# adafruit_flora_mainboard_2.net
KiCad netlist of a schematic drawn in Altium Designer
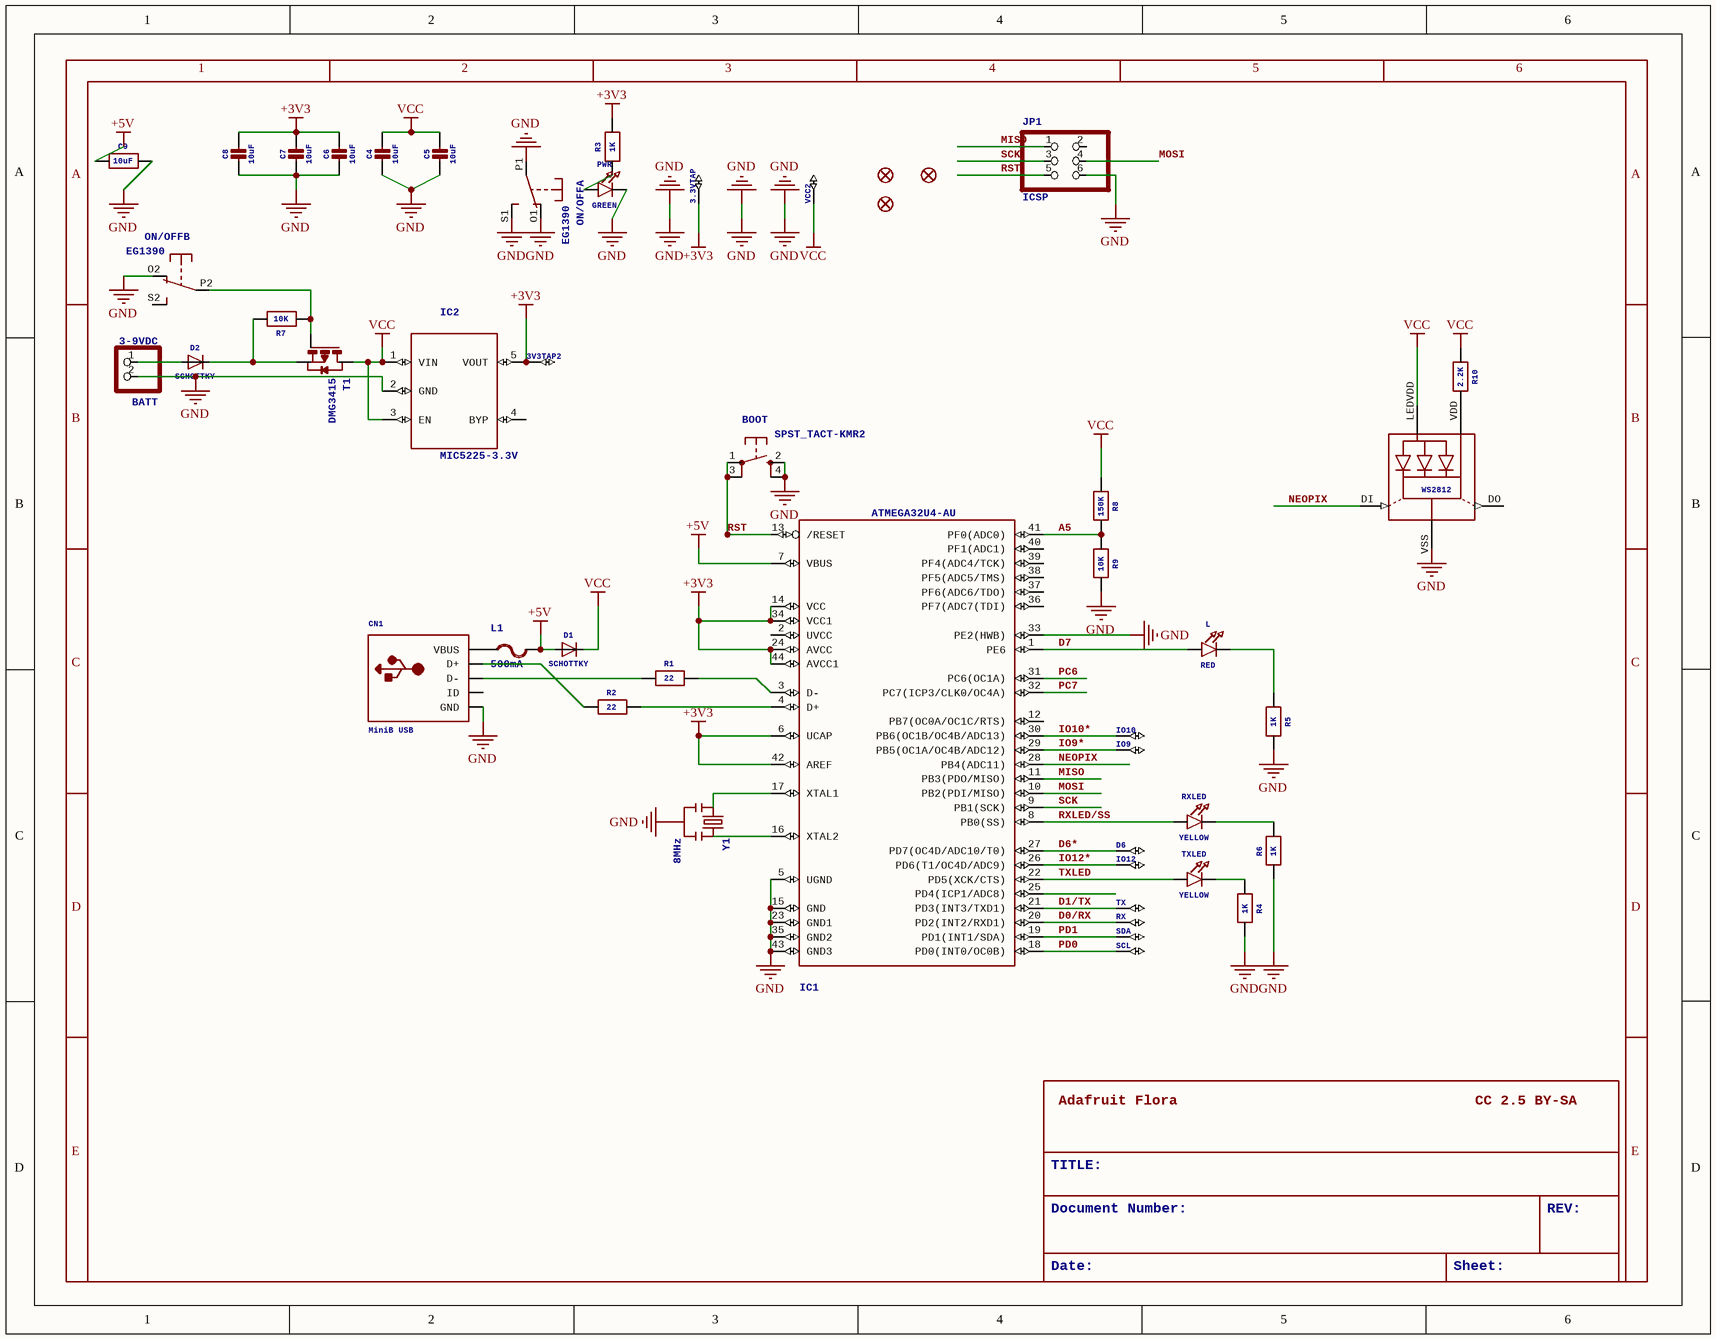
[diagram p0: adafruit flora mainboard 2.SchDoc]

(export (version "E")
  (design (tool "Eeschema 10.0.6"))
  (components
    (comp (ref "3.3VTAP")
      (value "SEWTAP-2.0IN")
      (footprint "SEWINGTAP_2.0")
      (libsource (lib "adafruit") (part "SEWTAP-2.0IN"))
    )
    (comp (ref "3V3TAP2")
      (value "SEWTAP-2.0IN")
      (footprint "SEWINGTAP_2.0")
      (libsource (lib "adafruit") (part "SEWTAP-2.0IN"))
    )
    (comp (ref "BATT")
      (value "3-9VDC")
      (footprint "JST-PH-2-SMT-RA")
      (libsource (lib "adafruit") (part "JST_2PIN-SMT-RA"))
    )
    (comp (ref "BOOT")
      (value "SPST_TACT-KMR2")
      (footprint "KMR2")
      (description "SMT 6mm switch, EVQQ2 series    http://www.ladyada.net/library/eagle")
      (libsource (lib "adafruit") (part "SPST_TACT-KMR2"))
    )
    (comp (ref "C4")
      (value "10uF")
      (footprint "0805-NO")
      (libsource (lib "microbuilder") (part "CAP_CERAMIC0805-NOOUTLINE"))
    )
    (comp (ref "C5")
      (value "10uF")
      (footprint "0805-NO")
      (libsource (lib "microbuilder") (part "CAP_CERAMIC0805-NOOUTLINE"))
    )
    (comp (ref "C6")
      (value "10uF")
      (footprint "0805-NO")
      (libsource (lib "microbuilder") (part "CAP_CERAMIC0805-NOOUTLINE"))
    )
    (comp (ref "C7")
      (value "10uF")
      (footprint "0805-NO")
      (libsource (lib "microbuilder") (part "CAP_CERAMIC0805-NOOUTLINE"))
    )
    (comp (ref "C8")
      (value "10uF")
      (footprint "0805-NO")
      (libsource (lib "microbuilder") (part "CAP_CERAMIC0805-NOOUTLINE"))
    )
    (comp (ref "C9")
      (value "10uF")
      (footprint "_0805MP")
      (libsource (lib "microbuilder") (part "RESISTOR_0805MP"))
    )
    (comp (ref "CN1")
      (value "MiniB USB")
      (footprint "4UCONN_20329")
      (description "USB ConnectorsUSBMINIB - Surface Mount Female Mini-B USB Connector    4UConnector: 06564")
      (libsource (lib "microbuilder") (part "USBMICRO_20329"))
    )
    (comp (ref "D1")
      (value "SCHOTTKY")
      (footprint "SOD-123")
      (libsource (lib "microbuilder") (part "DIODESOD-123"))
    )
    (comp (ref "D2")
      (value "SCHOTTKY")
      (footprint "SOD-123")
      (libsource (lib "microbuilder") (part "DIODESOD-123"))
    )
    (comp (ref "D6")
      (value "SEWTAP-2.0IN")
      (footprint "SEWINGTAP_2.0")
      (libsource (lib "adafruit") (part "SEWTAP-2.0IN"))
    )
    (comp (ref "IC1")
      (value "ATMEGA32U4-AU")
      (footprint "TQFP44")
      (fields (field (name "LIBRARYNAME") "adaprog"))
      (libsource (lib "adaprog") (part "ATMEGA32U4-AU"))
    )
    (comp (ref "IC2")
      (value "MIC5225-3.3V")
      (footprint "SOT23-5L")
      (libsource (lib "adafruit") (part "LP298XS"))
    )
    (comp (ref "IO9")
      (value "SEWTAP-2.0IN")
      (footprint "SEWINGTAP_2.0")
      (libsource (lib "adafruit") (part "SEWTAP-2.0IN"))
    )
    (comp (ref "IO10")
      (value "SEWTAP-2.0IN")
      (footprint "SEWINGTAP_2.0")
      (libsource (lib "adafruit") (part "SEWTAP-2.0IN"))
    )
    (comp (ref "IO12")
      (value "SEWTAP-2.0IN")
      (footprint "SEWINGTAP_2.0")
      (libsource (lib "adafruit") (part "SEWTAP-2.0IN"))
    )
    (comp (ref "JP1")
      (value "ICSP")
      (footprint "2X03")
      (description "PIN HEADER")
      (fields (field (name "LIBRARYNAME") "pinhead"))
      (libsource (lib "pinhead") (part "PINHD-2X3"))
    )
    (comp (ref "L")
      (value "RED")
      (footprint "CHIPLED_0805_NOOUTLINE")
      (libsource (lib "microbuilder") (part "LED0805_NOOUTLINE"))
    )
    (comp (ref "L1")
      (value "500mA")
      (footprint "R1206")
      (description "PTC fuses, resettable thermistors")
      (libsource (lib "adafruit") (part "PTCFUSE-1206"))
    )
    (comp (ref "LED1")
      (value "WS2812")
      (footprint "WS2812")
      (fields (field (name "WS2812") "WS2812"))
      (libsource (lib "adafruit") (part "WS2812"))
    )
    (comp (ref "ON/OFF")
      (value "EG1390")
      (footprint "EG1390")
      (libsource (lib "adafruit") (part "DPDT-EG1390"))
    )
    (comp (ref "PWR")
      (value "GREEN")
      (footprint "CHIPLED_0805_NOOUTLINE")
      (libsource (lib "microbuilder") (part "LED0805_NOOUTLINE"))
    )
    (comp (ref "R1")
      (value "22")
      (footprint "0805-NO")
      (libsource (lib "microbuilder") (part "RESISTOR0805_NOOUTLINE"))
    )
    (comp (ref "R2")
      (value "22")
      (footprint "0805-NO")
      (libsource (lib "microbuilder") (part "RESISTOR0805_NOOUTLINE"))
    )
    (comp (ref "R3")
      (value "1K")
      (footprint "_0805MP")
      (libsource (lib "microbuilder") (part "RESISTOR_0805MP"))
    )
    (comp (ref "R4")
      (value "1K")
      (footprint "_0805MP")
      (libsource (lib "microbuilder") (part "RESISTOR_0805MP"))
    )
    (comp (ref "R5")
      (value "1K")
      (footprint "0805-NO")
      (libsource (lib "microbuilder") (part "RESISTOR0805_NOOUTLINE"))
    )
    (comp (ref "R6")
      (value "1K")
      (footprint "0805-NO")
      (libsource (lib "microbuilder") (part "RESISTOR0805_NOOUTLINE"))
    )
    (comp (ref "R7")
      (value "10K")
      (footprint "_0805MP")
      (libsource (lib "microbuilder") (part "RESISTOR_0805MP"))
    )
    (comp (ref "R8")
      (value "150K")
      (footprint "0805-NO")
      (libsource (lib "microbuilder") (part "RESISTOR0805_NOOUTLINE"))
    )
    (comp (ref "R9")
      (value "10K")
      (footprint "0805-NO")
      (libsource (lib "microbuilder") (part "RESISTOR0805_NOOUTLINE"))
    )
    (comp (ref "R10")
      (value "2.2K")
      (footprint "0805-NO")
      (libsource (lib "microbuilder") (part "RESISTOR0805_NOOUTLINE"))
    )
    (comp (ref "RX")
      (value "SEWTAP-2.0IN")
      (footprint "SEWINGTAP_2.0")
      (libsource (lib "adafruit") (part "SEWTAP-2.0IN"))
    )
    (comp (ref "RXLED")
      (value "YELLOW")
      (footprint "CHIPLED_0805_NOOUTLINE")
      (libsource (lib "microbuilder") (part "LED0805_NOOUTLINE"))
    )
    (comp (ref "SCL")
      (value "SEWTAP-2.0IN")
      (footprint "SEWINGTAP_2.0")
      (libsource (lib "adafruit") (part "SEWTAP-2.0IN"))
    )
    (comp (ref "SDA")
      (value "SEWTAP-2.0IN")
      (footprint "SEWINGTAP_2.0")
      (libsource (lib "adafruit") (part "SEWTAP-2.0IN"))
    )
    (comp (ref "T1")
      (value "DMG3415")
      (footprint "SOT-23")
      (description "MOS FET")
      (libsource (lib "zetex") (part "PMOSSOT23"))
    )
    (comp (ref "TX")
      (value "SEWTAP-2.0IN")
      (footprint "SEWINGTAP_2.0")
      (libsource (lib "adafruit") (part "SEWTAP-2.0IN"))
    )
    (comp (ref "TXLED")
      (value "YELLOW")
      (footprint "CHIPLED_0805_NOOUTLINE")
      (libsource (lib "microbuilder") (part "LED0805_NOOUTLINE"))
    )
    (comp (ref "U$2")
      (value "FIDUCIAL\"\"")
      (footprint "FIDUCIAL_1MM")
      (description "Fiducial Alignment Points   Various fiducial points for machine vision alignment.")
      (libsource (lib "microbuilder") (part "FIDUCIAL{dblquote}{dblquote}"))
    )
    (comp (ref "U$3")
      (value "FIDUCIAL\"\"")
      (footprint "FIDUCIAL_1MM")
      (description "Fiducial Alignment Points   Various fiducial points for machine vision alignment.")
      (libsource (lib "microbuilder") (part "FIDUCIAL{dblquote}{dblquote}"))
    )
    (comp (ref "U$6")
      (value "FIDUCIAL\"\"")
      (footprint "FIDUCIAL_1MM")
      (description "Fiducial Alignment Points   Various fiducial points for machine vision alignment.")
      (libsource (lib "microbuilder") (part "FIDUCIAL{dblquote}{dblquote}"))
    )
    (comp (ref "VCC2")
      (value "SEWTAP-2.0IN")
      (footprint "SEWINGTAP_2.0")
      (libsource (lib "adafruit") (part "SEWTAP-2.0IN"))
    )
    (comp (ref "Y1")
      (value "8MHz")
      (footprint "RESONATOR-SMD")
      (libsource (lib "SparkFun") (part "RESONATORSMD"))
    )
  )
  (nets
    (net (code "1") (name "+3V3") (class "Default")
      (node (ref "3.3VTAP") (pin "P$1") (pinfunction "SEW_P$1") (pintype "bidirectional"))
      (node (ref "3V3TAP2") (pin "P$1") (pinfunction "SEW_P$1") (pintype "bidirectional"))
      (node (ref "C6") (pin "1") (pinfunction "1_1") (pintype "passive"))
      (node (ref "C7") (pin "1") (pinfunction "1_1") (pintype "passive"))
      (node (ref "C8") (pin "1") (pinfunction "1_1") (pintype "passive"))
      (node (ref "IC1") (pin "14") (pinfunction "VCC_14") (pintype "bidirectional"))
      (node (ref "IC1") (pin "24") (pinfunction "AVCC_24") (pintype "bidirectional"))
      (node (ref "IC1") (pin "34") (pinfunction "VCC1_34") (pintype "bidirectional"))
      (node (ref "IC1") (pin "42") (pinfunction "AREF_42") (pintype "bidirectional"))
      (node (ref "IC1") (pin "44") (pinfunction "AVCC1_44") (pintype "bidirectional"))
      (node (ref "IC1") (pin "6") (pinfunction "UCAP_6") (pintype "bidirectional"))
      (node (ref "IC2") (pin "5") (pinfunction "VOUT_5") (pintype "bidirectional"))
      (node (ref "R3") (pin "2") (pinfunction "2_2") (pintype "passive"))
    )
    (net (code "2") (name "+5V") (class "Default")
      (node (ref "C9") (pin "1") (pinfunction "1_1") (pintype "passive"))
      (node (ref "D1") (pin "A") (pinfunction "A_A") (pintype "passive"))
      (node (ref "IC1") (pin "7") (pinfunction "VBUS_7") (pintype "bidirectional"))
      (node (ref "L1") (pin "2") (pinfunction "2_2") (pintype "passive"))
    )
    (net (code "3") (name "/A5") (class "Default")
      (node (ref "IC1") (pin "41") (pinfunction "PF0(ADC0)_41") (pintype "bidirectional"))
      (node (ref "R8") (pin "2") (pinfunction "2_2") (pintype "passive"))
      (node (ref "R9") (pin "1") (pinfunction "1_1") (pintype "passive"))
    )
    (net (code "4") (name "/D0{slash}RX") (class "Default")
      (node (ref "IC1") (pin "20") (pinfunction "PD2(INT2/RXD1)_20") (pintype "bidirectional"))
      (node (ref "RX") (pin "P$1") (pinfunction "SEW_P$1") (pintype "bidirectional"))
    )
    (net (code "5") (name "/D1{slash}TX") (class "Default")
      (node (ref "IC1") (pin "21") (pinfunction "PD3(INT3/TXD1)_21") (pintype "bidirectional"))
      (node (ref "TX") (pin "P$1") (pinfunction "SEW_P$1") (pintype "bidirectional"))
    )
    (net (code "6") (name "/D6*") (class "Default")
      (node (ref "D6") (pin "P$1") (pinfunction "SEW_P$1") (pintype "bidirectional"))
      (node (ref "IC1") (pin "27") (pinfunction "PD7(OC4D/ADC10/T0)_27") (pintype "bidirectional"))
    )
    (net (code "7") (name "/D7") (class "Default")
      (node (ref "IC1") (pin "1") (pinfunction "PE6_1") (pintype "bidirectional"))
      (node (ref "L") (pin "A") (pinfunction "A_A") (pintype "passive"))
    )
    (net (code "8") (name "/IO9*") (class "Default")
      (node (ref "IC1") (pin "29") (pinfunction "PB5(OC1A/OC4B/ADC12)_29") (pintype "bidirectional"))
      (node (ref "IO9") (pin "P$1") (pinfunction "SEW_P$1") (pintype "bidirectional"))
    )
    (net (code "9") (name "/IO10*") (class "Default")
      (node (ref "IC1") (pin "30") (pinfunction "PB6(OC1B/OC4B/ADC13)_30") (pintype "bidirectional"))
      (node (ref "IO10") (pin "P$1") (pinfunction "SEW_P$1") (pintype "bidirectional"))
    )
    (net (code "10") (name "/IO12*") (class "Default")
      (node (ref "IC1") (pin "26") (pinfunction "PD6(T1/OC4D/ADC9)_26") (pintype "bidirectional"))
      (node (ref "IO12") (pin "P$1") (pinfunction "SEW_P$1") (pintype "bidirectional"))
    )
    (net (code "11") (name "/MISO") (class "Default")
      (node (ref "IC1") (pin "11") (pinfunction "PB3(PDO/MISO)_11") (pintype "bidirectional"))
      (node (ref "JP1") (pin "1") (pinfunction "1_1") (pintype "passive"))
    )
    (net (code "12") (name "/MOSI") (class "Default")
      (node (ref "IC1") (pin "10") (pinfunction "PB2(PDI/MISO)_10") (pintype "bidirectional"))
      (node (ref "JP1") (pin "4") (pinfunction "4_4") (pintype "passive"))
    )
    (net (code "13") (name "/NEOPIX") (class "Default")
      (node (ref "IC1") (pin "28") (pinfunction "PB4(ADC11)_28") (pintype "bidirectional"))
      (node (ref "LED1") (pin "DI") (pinfunction "DI_DI") (pintype "input"))
    )
    (net (code "14") (name "/PC6") (class "Default")
      (node (ref "IC1") (pin "31") (pinfunction "PC6(OC1A)_31") (pintype "bidirectional"))
    )
    (net (code "15") (name "/PC7") (class "Default")
      (node (ref "IC1") (pin "32") (pinfunction "PC7(ICP3/CLK0/OC4A)_32") (pintype "bidirectional"))
    )
    (net (code "16") (name "/PD0") (class "Default")
      (node (ref "IC1") (pin "18") (pinfunction "PD0(INT0/OC0B)_18") (pintype "bidirectional"))
      (node (ref "SCL") (pin "P$1") (pinfunction "SEW_P$1") (pintype "bidirectional"))
    )
    (net (code "17") (name "/PD1") (class "Default")
      (node (ref "IC1") (pin "19") (pinfunction "PD1(INT1/SDA)_19") (pintype "bidirectional"))
      (node (ref "SDA") (pin "P$1") (pinfunction "SEW_P$1") (pintype "bidirectional"))
    )
    (net (code "18") (name "/RST") (class "Default")
      (node (ref "BOOT") (pin "1") (pinfunction "P_1") (pintype "passive"))
      (node (ref "BOOT") (pin "3") (pinfunction "P1_3") (pintype "passive"))
      (node (ref "IC1") (pin "13") (pinfunction "/RESET_13") (pintype "bidirectional"))
      (node (ref "JP1") (pin "5") (pinfunction "5_5") (pintype "passive"))
    )
    (net (code "19") (name "/RXLED{slash}SS") (class "Default")
      (node (ref "IC1") (pin "8") (pinfunction "PB0(SS)_8") (pintype "bidirectional"))
      (node (ref "RXLED") (pin "A") (pinfunction "A_A") (pintype "passive"))
    )
    (net (code "20") (name "/SCK") (class "Default")
      (node (ref "IC1") (pin "9") (pinfunction "PB1(SCK)_9") (pintype "bidirectional"))
      (node (ref "JP1") (pin "3") (pinfunction "3_3") (pintype "passive"))
    )
    (net (code "21") (name "/TXLED") (class "Default")
      (node (ref "IC1") (pin "22") (pinfunction "PD5(XCK/CTS)_22") (pintype "bidirectional"))
      (node (ref "TXLED") (pin "A") (pinfunction "A_A") (pintype "passive"))
    )
    (net (code "22") (name "GND") (class "Default")
      (node (ref "BATT") (pin "2") (pinfunction "1_2") (pintype "passive"))
      (node (ref "BOOT") (pin "2") (pinfunction "S_2") (pintype "passive"))
      (node (ref "BOOT") (pin "4") (pinfunction "S1_4") (pintype "passive"))
      (node (ref "C4") (pin "2") (pinfunction "2_2") (pintype "passive"))
      (node (ref "C5") (pin "2") (pinfunction "2_2") (pintype "passive"))
      (node (ref "C6") (pin "2") (pinfunction "2_2") (pintype "passive"))
      (node (ref "C7") (pin "2") (pinfunction "2_2") (pintype "passive"))
      (node (ref "C8") (pin "2") (pinfunction "2_2") (pintype "passive"))
      (node (ref "C9") (pin "2") (pinfunction "2_2") (pintype "passive"))
      (node (ref "CN1") (pin "BASE@1_BASE@2_GND_SPRT@1_SPRT@2_SPRT@3_SPRT@4") (pinfunction "GND_BASE@1_BASE@2_GND_SPRT@1_SPRT@2_SPRT@3_SPRT@4") (pintype "power_in"))
      (node (ref "IC1") (pin "15") (pinfunction "GND_15") (pintype "bidirectional"))
      (node (ref "IC1") (pin "23") (pinfunction "GND1_23") (pintype "bidirectional"))
      (node (ref "IC1") (pin "33") (pinfunction "PE2(HWB)_33") (pintype "bidirectional"))
      (node (ref "IC1") (pin "35") (pinfunction "GND2_35") (pintype "bidirectional"))
      (node (ref "IC1") (pin "43") (pinfunction "GND3_43") (pintype "bidirectional"))
      (node (ref "IC1") (pin "5") (pinfunction "UGND_5") (pintype "bidirectional"))
      (node (ref "IC2") (pin "2") (pinfunction "GND_2") (pintype "bidirectional"))
      (node (ref "JP1") (pin "6") (pinfunction "6_6") (pintype "passive"))
      (node (ref "LED1") (pin "VSS") (pinfunction "GND_VSS") (pintype "power_in"))
      (node (ref "ON/OFF") (pin "O1") (pinfunction "O_O1") (pintype "passive"))
      (node (ref "ON/OFF") (pin "O2") (pinfunction "O_O2") (pintype "passive"))
      (node (ref "ON/OFF") (pin "P1") (pinfunction "P_P1") (pintype "passive"))
      (node (ref "ON/OFF") (pin "S1") (pinfunction "S_S1") (pintype "passive"))
      (node (ref "PWR") (pin "C") (pinfunction "C_C") (pintype "passive"))
      (node (ref "R4") (pin "2") (pinfunction "2_2") (pintype "passive"))
      (node (ref "R5") (pin "2") (pinfunction "2_2") (pintype "passive"))
      (node (ref "R6") (pin "1") (pinfunction "1_1") (pintype "passive"))
      (node (ref "R9") (pin "2") (pinfunction "2_2") (pintype "passive"))
      (node (ref "Y1") (pin "2") (pinfunction "2_2") (pintype "passive"))
    )
    (net (code "23") (name "Net-(BATT-2)") (class "Default")
      (node (ref "BATT") (pin "1") (pinfunction "2_1") (pintype "passive"))
      (node (ref "D2") (pin "A") (pinfunction "A_A") (pintype "passive"))
    )
    (net (code "24") (name "Net-(CN1-PadD+)") (class "Default")
      (node (ref "CN1") (pin "D+") (pinfunction "D+_D+") (pintype "bidirectional"))
      (node (ref "R2") (pin "1") (pinfunction "1_1") (pintype "passive"))
    )
    (net (code "25") (name "Net-(CN1-PadD-)") (class "Default")
      (node (ref "CN1") (pin "D-") (pinfunction "D-_D-") (pintype "bidirectional"))
      (node (ref "R1") (pin "1") (pinfunction "1_1") (pintype "passive"))
    )
    (net (code "26") (name "Net-(CN1-PadVBUS)") (class "Default")
      (node (ref "CN1") (pin "VBUS") (pinfunction "VBUS_VBUS") (pintype "power_in"))
      (node (ref "L1") (pin "1") (pinfunction "1_1") (pintype "passive"))
    )
    (net (code "27") (name "Net-(IC1-D+)") (class "Default")
      (node (ref "IC1") (pin "4") (pinfunction "D+_4") (pintype "bidirectional"))
      (node (ref "R2") (pin "2") (pinfunction "2_2") (pintype "passive"))
    )
    (net (code "28") (name "Net-(IC1-D-)") (class "Default")
      (node (ref "IC1") (pin "3") (pinfunction "D-_3") (pintype "bidirectional"))
      (node (ref "R1") (pin "2") (pinfunction "2_2") (pintype "passive"))
    )
    (net (code "29") (name "Net-(IC1-XTAL1)") (class "Default")
      (node (ref "IC1") (pin "17") (pinfunction "XTAL1_17") (pintype "bidirectional"))
      (node (ref "Y1") (pin "1") (pinfunction "1_1") (pintype "passive"))
    )
    (net (code "30") (name "Net-(IC1-XTAL2)") (class "Default")
      (node (ref "IC1") (pin "16") (pinfunction "XTAL2_16") (pintype "bidirectional"))
      (node (ref "Y1") (pin "3") (pinfunction "3_3") (pintype "passive"))
    )
    (net (code "31") (name "Net-(L-PadC)") (class "Default")
      (node (ref "L") (pin "C") (pinfunction "C_C") (pintype "passive"))
      (node (ref "R5") (pin "1") (pinfunction "1_1") (pintype "passive"))
    )
    (net (code "32") (name "Net-(LED1-PadVDD)") (class "Default")
      (node (ref "LED1") (pin "VDD") (pinfunction "VDD_VDD") (pintype "power_in"))
      (node (ref "R10") (pin "2") (pinfunction "2_2") (pintype "passive"))
    )
    (net (code "33") (name "Net-(ON/OFFB-P)") (class "Default")
      (node (ref "ON/OFF") (pin "P2") (pinfunction "P_P2") (pintype "passive"))
      (node (ref "R7") (pin "1") (pinfunction "1_1") (pintype "passive"))
      (node (ref "T1") (pin "3") (pinfunction "G_3") (pintype "passive"))
    )
    (net (code "34") (name "Net-(PWR-PadA)") (class "Default")
      (node (ref "PWR") (pin "A") (pinfunction "A_A") (pintype "passive"))
      (node (ref "R3") (pin "1") (pinfunction "1_1") (pintype "passive"))
    )
    (net (code "35") (name "Net-(R4-Pad1)") (class "Default")
      (node (ref "R4") (pin "1") (pinfunction "1_1") (pintype "passive"))
      (node (ref "TXLED") (pin "C") (pinfunction "C_C") (pintype "passive"))
    )
    (net (code "36") (name "Net-(R6-Pad2)") (class "Default")
      (node (ref "R6") (pin "2") (pinfunction "2_2") (pintype "passive"))
      (node (ref "RXLED") (pin "C") (pinfunction "C_C") (pintype "passive"))
    )
    (net (code "37") (name "Net-(T1-S)") (class "Default")
      (node (ref "D2") (pin "C") (pinfunction "C_C") (pintype "passive"))
      (node (ref "R7") (pin "2") (pinfunction "2_2") (pintype "passive"))
      (node (ref "T1") (pin "2") (pinfunction "S_2") (pintype "passive"))
    )
    (net (code "38") (name "VCC") (class "Default")
      (node (ref "C4") (pin "1") (pinfunction "1_1") (pintype "passive"))
      (node (ref "C5") (pin "1") (pinfunction "1_1") (pintype "passive"))
      (node (ref "D1") (pin "C") (pinfunction "C_C") (pintype "passive"))
      (node (ref "IC2") (pin "1") (pinfunction "VIN_1") (pintype "bidirectional"))
      (node (ref "IC2") (pin "3") (pinfunction "EN_3") (pintype "bidirectional"))
      (node (ref "LED1") (pin "LEDVDD") (pinfunction "LEDVDD_LEDVDD") (pintype "power_in"))
      (node (ref "R10") (pin "1") (pinfunction "1_1") (pintype "passive"))
      (node (ref "R8") (pin "1") (pinfunction "1_1") (pintype "passive"))
      (node (ref "T1") (pin "1") (pinfunction "D_1") (pintype "passive"))
      (node (ref "VCC2") (pin "P$1") (pinfunction "SEW_P$1") (pintype "bidirectional"))
    )
    (net (code "39") (name "unconnected-(CN1-PadID)") (class "Default")
      (node (ref "CN1") (pin "ID") (pinfunction "ID_ID") (pintype "bidirectional"))
    )
    (net (code "40") (name "unconnected-(IC1-PB7(OC0A{slash}OC1C{slash}RTS)-Pad12)") (class "Default")
      (node (ref "IC1") (pin "12") (pinfunction "PB7(OC0A/OC1C/RTS)_12") (pintype "bidirectional"))
    )
    (net (code "41") (name "unconnected-(IC1-PD4(ICP1{slash}ADC8)-Pad25)") (class "Default")
      (node (ref "IC1") (pin "25") (pinfunction "PD4(ICP1/ADC8)_25") (pintype "bidirectional"))
    )
    (net (code "42") (name "unconnected-(IC1-PF1(ADC1)-Pad40)") (class "Default")
      (node (ref "IC1") (pin "40") (pinfunction "PF1(ADC1)_40") (pintype "bidirectional"))
    )
    (net (code "43") (name "unconnected-(IC1-PF4(ADC4{slash}TCK)-Pad39)") (class "Default")
      (node (ref "IC1") (pin "39") (pinfunction "PF4(ADC4/TCK)_39") (pintype "bidirectional"))
    )
    (net (code "44") (name "unconnected-(IC1-PF5(ADC5{slash}TMS)-Pad38)") (class "Default")
      (node (ref "IC1") (pin "38") (pinfunction "PF5(ADC5/TMS)_38") (pintype "bidirectional"))
    )
    (net (code "45") (name "unconnected-(IC1-PF6(ADC6{slash}TDO)-Pad37)") (class "Default")
      (node (ref "IC1") (pin "37") (pinfunction "PF6(ADC6/TDO)_37") (pintype "bidirectional"))
    )
    (net (code "46") (name "unconnected-(IC1-PF7(ADC7(TDI)-Pad36)") (class "Default")
      (node (ref "IC1") (pin "36") (pinfunction "PF7(ADC7(TDI)_36") (pintype "bidirectional"))
    )
    (net (code "47") (name "unconnected-(IC1-UVCC-Pad2)") (class "Default")
      (node (ref "IC1") (pin "2") (pinfunction "UVCC_2") (pintype "bidirectional"))
    )
    (net (code "48") (name "unconnected-(IC2-BYP-Pad4)") (class "Default")
      (node (ref "IC2") (pin "4") (pinfunction "BYP_4") (pintype "bidirectional"))
    )
    (net (code "49") (name "unconnected-(JP1-Pad2)") (class "Default")
      (node (ref "JP1") (pin "2") (pinfunction "2_2") (pintype "passive"))
    )
    (net (code "50") (name "unconnected-(LED1-PadDO)") (class "Default")
      (node (ref "LED1") (pin "DO") (pinfunction "DO_DO") (pintype "output"))
    )
    (net (code "51") (name "unconnected-(ON/OFFB-S-PadS2)") (class "Default")
      (node (ref "ON/OFF") (pin "S2") (pinfunction "S_S2") (pintype "passive"))
    )
  )
)
